# Sheet1.net
KiCad netlist of a schematic drawn in Altium Designer
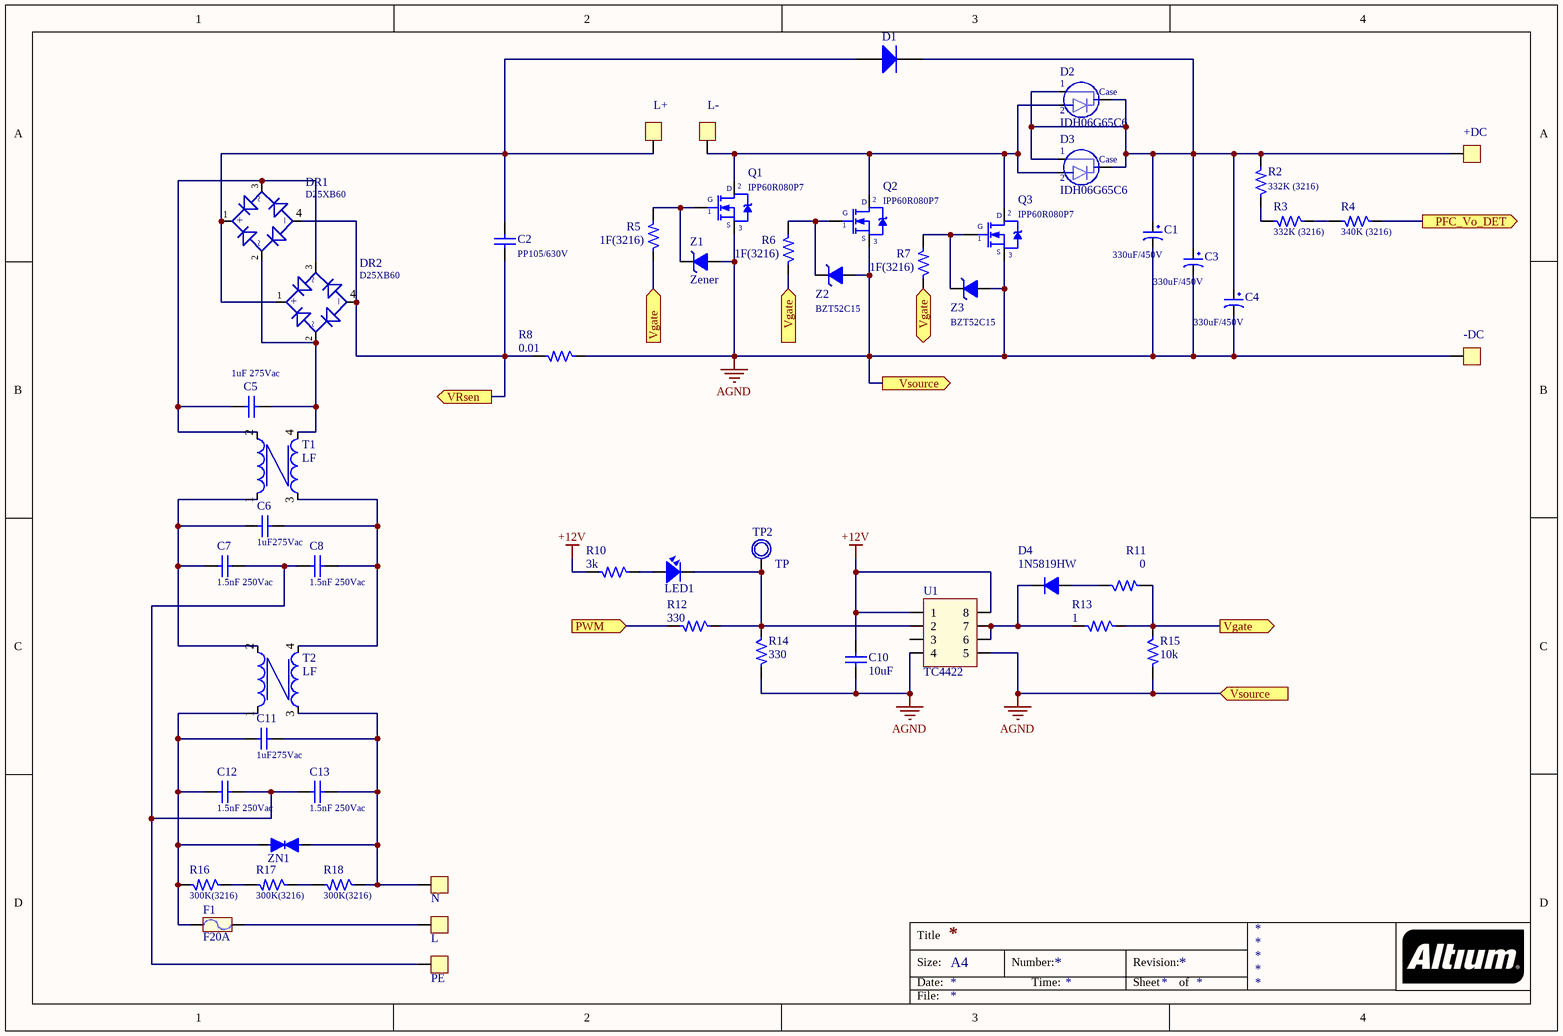
[diagram p0: Sheet1.SchDoc]

(export (version "E")
  (design (tool "Eeschema 10.0.6"))
  (components
    (comp (ref "+DC") (value "ERNI") (footprint "Connector") (libsource (lib "Tien_Lib") (part "Connector")))
    (comp (ref "-DC") (value "ERNI") (footprint "Connector") (libsource (lib "Tien_Lib") (part "Connector")))
    (comp (ref "C1")
      (value "330uF/450V")
      (footprint "Capacitor")
      (description "Cap 10000uF/63V")
      (libsource (lib "syhaunguyen") (part "CP9"))
    )
    (comp (ref "C2")
      (value "PP105/630V")
      (footprint "C1uF 28mm")
      (description "Capacitor (Semiconductor SIM Model)")
      (fields (field (name "PUBLISHER") "Altium Limited"))
      (libsource (lib "syhaunguyen") (part "Cap Semi_3"))
    )
    (comp (ref "C3")
      (value "330uF/450V")
      (footprint "Capacitor")
      (description "Cap 10000uF/63V")
      (libsource (lib "syhaunguyen") (part "CP9"))
    )
    (comp (ref "C4")
      (value "330uF/450V")
      (footprint "Capacitor")
      (description "Cap 10000uF/63V")
      (libsource (lib "syhaunguyen") (part "CP9"))
    )
    (comp (ref "C5")
      (value "1uF 275Vac")
      (footprint "CAP 11x22")
      (description "Capacitor (Semiconductor SIM Model)")
      (fields (field (name "PUBLISHER") "Altium Limited"))
      (libsource (lib "syhaunguyen") (part "Cap Semi_3"))
    )
    (comp (ref "C6")
      (value "1uF275Vac")
      (footprint "CAP 11x22")
      (description "Capacitor (Semiconductor SIM Model)")
      (fields (field (name "PUBLISHER") "Altium Limited"))
      (libsource (lib "syhaunguyen") (part "Cap Semi_3"))
    )
    (comp (ref "C7")
      (value "1.5nF 250Vac")
      (footprint "CN4")
      (description "Capacitor (Semiconductor SIM Model)")
      (fields (field (name "PUBLISHER") "Altium Limited"))
      (libsource (lib "syhaunguyen") (part "Cap Semi_3"))
    )
    (comp (ref "C8")
      (value "1.5nF 250Vac")
      (footprint "CN4")
      (description "Capacitor (Semiconductor SIM Model)")
      (fields (field (name "PUBLISHER") "Altium Limited"))
      (libsource (lib "syhaunguyen") (part "Cap Semi_3"))
    )
    (comp (ref "C10")
      (value "10uF")
      (footprint "SM-CAP-0805")
      (description "Capacitor (Semiconductor SIM Model)")
      (fields (field (name "PUBLISHER") "Altium Limited"))
      (libsource (lib "syhaunguyen") (part "Cap Semi_3"))
    )
    (comp (ref "C11")
      (value "1uF275Vac")
      (footprint "CAP 11x22")
      (description "Capacitor (Semiconductor SIM Model)")
      (fields (field (name "PUBLISHER") "Altium Limited"))
      (libsource (lib "syhaunguyen") (part "Cap Semi_3"))
    )
    (comp (ref "C12")
      (value "1.5nF 250Vac")
      (footprint "CN4")
      (description "Capacitor (Semiconductor SIM Model)")
      (fields (field (name "PUBLISHER") "Altium Limited"))
      (libsource (lib "syhaunguyen") (part "Cap Semi_3"))
    )
    (comp (ref "C13")
      (value "1.5nF 250Vac")
      (footprint "CN4")
      (description "Capacitor (Semiconductor SIM Model)")
      (fields (field (name "PUBLISHER") "Altium Limited"))
      (libsource (lib "syhaunguyen") (part "Cap Semi_3"))
    )
    (comp (ref "D1")
      (value "Diode")
      (footprint "D5AN")
      (description "Default Diode")
      (fields (field (name "PUBLISHER") "Altium Limited"))
      (libsource (lib "syhaunguyen") (part "Diode"))
    )
    (comp (ref "D2")
      (value "IDH06G65C6")
      (footprint "TO-263 Diode")
      (libsource (lib "UC3854") (part "CSD06060"))
    )
    (comp (ref "D3")
      (value "IDH06G65C6")
      (footprint "TO-263 Diode")
      (libsource (lib "UC3854") (part "CSD06060"))
    )
    (comp (ref "D4")
      (value "1N5819HW")
      (footprint "BZT52C15")
      (description "D0.5A")
      (libsource (lib "syhaunguyen") (part "D0.5A"))
    )
    (comp (ref "DR1")
      (value "D25XB60")
      (footprint "D25XB60")
      (libsource (lib "UC3854") (part "Bridge Rectifier"))
    )
    (comp (ref "DR2")
      (value "D25XB60")
      (footprint "D25XB60")
      (libsource (lib "UC3854") (part "Bridge Rectifier"))
    )
    (comp (ref "F1")
      (value "F20A")
      (footprint "Fuse")
      (description "Fuse")
      (fields (field (name "DESIGNED BY") "VanDungEvn"))
      (libsource (lib "syhaunguyen") (part "Fuse"))
    )
    (comp (ref "L") (value "ERNI") (footprint "Connector") (libsource (lib "Tien_Lib") (part "Connector")))
    (comp (ref "L+") (value "ERNI") (footprint "Connector") (libsource (lib "") (part "Connector_1")))
    (comp (ref "L-") (value "ERNI") (footprint "Connector") (libsource (lib "") (part "Connector_1")))
    (comp (ref "LED1")
      (value "LED")
      (footprint "SM-LED-0805-Blue")
      (description "LED Single colour Green and Red")
      (libsource (lib "syhaunguyen") (part "LED"))
    )
    (comp (ref "N") (value "ERNI") (footprint "Connector") (libsource (lib "Tien_Lib") (part "Connector")))
    (comp (ref "PE") (value "ERNI") (footprint "Connector") (libsource (lib "Tien_Lib") (part "Connector")))
    (comp (ref "Q1")
      (value "IPP60R080P7")
      (footprint "TO-263 MOSFET")
      (description "MOSFET N - CHANNEL 500V - 0.75 - 8A - TO-220")
      (libsource (lib "syhaunguyen") (part "IRF840"))
    )
    (comp (ref "Q2")
      (value "IPP60R080P7")
      (footprint "TO-263 MOSFET")
      (description "MOSFET N - CHANNEL 500V - 0.75 - 8A - TO-220")
      (libsource (lib "syhaunguyen") (part "IRF840"))
    )
    (comp (ref "Q3")
      (value "IPP60R080P7")
      (footprint "TO-263 MOSFET")
      (description "MOSFET N - CHANNEL 500V - 0.75 - 8A - TO-220")
      (libsource (lib "syhaunguyen") (part "IRF840"))
    )
    (comp (ref "R2")
      (value "332K (3216)")
      (footprint "SM-RES-1206")
      (description "Resistor 1/4W")
      (libsource (lib "syhaunguyen") (part "R"))
    )
    (comp (ref "R3")
      (value "332K (3216)")
      (footprint "SM-RES-1206")
      (description "Resistor 1/4W")
      (libsource (lib "syhaunguyen") (part "R"))
    )
    (comp (ref "R4")
      (value "340K (3216)")
      (footprint "SM-RES-1206")
      (description "Resistor 1/4W")
      (libsource (lib "syhaunguyen") (part "R"))
    )
    (comp (ref "R5")
      (value "1F(3216)")
      (footprint "SM-RES-1206")
      (description "Resistor 1/4W")
      (libsource (lib "syhaunguyen") (part "R"))
    )
    (comp (ref "R6")
      (value "1F(3216)")
      (footprint "SM-RES-1206")
      (description "Resistor 1/4W")
      (libsource (lib "syhaunguyen") (part "R"))
    )
    (comp (ref "R7")
      (value "1F(3216)")
      (footprint "SM-RES-1206")
      (description "Resistor 1/4W")
      (libsource (lib "syhaunguyen") (part "R"))
    )
    (comp (ref "R8")
      (value "0.01")
      (footprint "WSHM2818")
      (description "Resistor 1/4W")
      (libsource (lib "syhaunguyen") (part "R"))
    )
    (comp (ref "R10")
      (value "3k")
      (footprint "SM-RES-0805")
      (description "Resistor 1/4W")
      (libsource (lib "syhaunguyen") (part "R"))
    )
    (comp (ref "R11")
      (value "0")
      (footprint "SM-RES-1206")
      (description "Resistor 1/4W")
      (libsource (lib "syhaunguyen") (part "R"))
    )
    (comp (ref "R12")
      (value "330")
      (footprint "SM-RES-0805")
      (description "Resistor 1/4W")
      (libsource (lib "syhaunguyen") (part "R"))
    )
    (comp (ref "R13")
      (value "1")
      (footprint "SM-RES-1206")
      (description "Resistor 1/4W")
      (libsource (lib "syhaunguyen") (part "R"))
    )
    (comp (ref "R14")
      (value "330")
      (footprint "SM-RES-0805")
      (description "Resistor 1/4W")
      (libsource (lib "syhaunguyen") (part "R"))
    )
    (comp (ref "R15")
      (value "10k")
      (footprint "SM-RES-0805")
      (description "Resistor 1/4W")
      (libsource (lib "syhaunguyen") (part "R"))
    )
    (comp (ref "R16")
      (value "300K(3216)")
      (footprint "SM-RES-1206")
      (description "Resistor 1/4W")
      (libsource (lib "syhaunguyen") (part "R"))
    )
    (comp (ref "R17")
      (value "300K(3216)")
      (footprint "SM-RES-1206")
      (description "Resistor 1/4W")
      (libsource (lib "syhaunguyen") (part "R"))
    )
    (comp (ref "R18")
      (value "300K(3216)")
      (footprint "SM-RES-1206")
      (description "Resistor 1/4W")
      (libsource (lib "syhaunguyen") (part "R"))
    )
    (comp (ref "T1")
      (value "LF")
      (footprint "EMI tranformer")
      (libsource (lib "UC3854") (part "IEMI filter"))
    )
    (comp (ref "T2")
      (value "LF")
      (footprint "EMI tranformer")
      (libsource (lib "UC3854") (part "IEMI filter"))
    )
    (comp (ref "TP2")
      (value "TP")
      (footprint "TP1")
      (description "Test Point")
      (libsource (lib "syhaunguyen") (part "TP1"))
    )
    (comp (ref "U1")
      (value "TC4422")
      (footprint "TC4422")
      (description "DIP8")
      (libsource (lib "syhaunguyen") (part "DIP8"))
    )
    (comp (ref "Z1") (value "Zener") (footprint "BZT52C15") (libsource (lib "syhaunguyen") (part "Zener")))
    (comp (ref "Z2") (value "BZT52C15") (footprint "BZT52C15") (libsource (lib "syhaunguyen") (part "Zener")))
    (comp (ref "Z3") (value "BZT52C15") (footprint "BZT52C15") (libsource (lib "syhaunguyen") (part "Zener")))
    (comp (ref "ZN1")
      (value "Z")
      (footprint "RT 7mm")
      (description "Zenner Protect AC in")
      (libsource (lib "syhaunguyen") (part "ZN"))
    )
  )
  (nets
    (net (code "1") (name "+12V") (class "Default")
      (node (ref "C10") (pin "1") (pinfunction "1_1") (pintype "passive"))
      (node (ref "R10") (pin "2") (pinfunction "2_2") (pintype "passive"))
      (node (ref "U1") (pin "1") (pinfunction "1_1") (pintype "passive"))
      (node (ref "U1") (pin "8") (pinfunction "8_8") (pintype "passive"))
    )
    (net (code "2") (name "/PFC_Vo_DET") (class "Default")
      (node (ref "R4") (pin "1") (pinfunction "1_1") (pintype "passive"))
    )
    (net (code "3") (name "/PWM") (class "Default")
      (node (ref "R12") (pin "2") (pinfunction "2_2") (pintype "passive"))
    )
    (net (code "4") (name "/VRsen") (class "Default")
      (node (ref "C2") (pin "1") (pinfunction "1_1") (pintype "passive"))
      (node (ref "DR1") (pin "4") (pinfunction "0_4") (pintype "passive"))
      (node (ref "DR2") (pin "4") (pinfunction "0_4") (pintype "passive"))
      (node (ref "R8") (pin "2") (pinfunction "2_2") (pintype "passive"))
    )
    (net (code "5") (name "/Vgate") (class "Default")
      (node (ref "R11") (pin "2") (pinfunction "2_2") (pintype "passive"))
      (node (ref "R13") (pin "1") (pinfunction "1_1") (pintype "passive"))
      (node (ref "R15") (pin "1") (pinfunction "1_1") (pintype "passive"))
      (node (ref "R5") (pin "1") (pinfunction "1_1") (pintype "passive"))
      (node (ref "R6") (pin "1") (pinfunction "1_1") (pintype "passive"))
      (node (ref "R7") (pin "1") (pinfunction "1_1") (pintype "passive"))
    )
    (net (code "6") (name "AGND") (class "Default")
      (node (ref "-DC") (pin "0") (pinfunction "0_0") (pintype "passive"))
      (node (ref "C1") (pin "2") (pinfunction "2_2") (pintype "passive"))
      (node (ref "C10") (pin "2") (pinfunction "2_2") (pintype "passive"))
      (node (ref "C3") (pin "2") (pinfunction "2_2") (pintype "passive"))
      (node (ref "C4") (pin "2") (pinfunction "2_2") (pintype "passive"))
      (node (ref "Q1") (pin "3") (pinfunction "S_3") (pintype "passive"))
      (node (ref "Q2") (pin "3") (pinfunction "S_3") (pintype "passive"))
      (node (ref "Q3") (pin "3") (pinfunction "S_3") (pintype "passive"))
      (node (ref "R14") (pin "2") (pinfunction "2_2") (pintype "passive"))
      (node (ref "R15") (pin "2") (pinfunction "2_2") (pintype "passive"))
      (node (ref "R8") (pin "1") (pinfunction "1_1") (pintype "passive"))
      (node (ref "U1") (pin "4") (pinfunction "4_4") (pintype "passive"))
      (node (ref "U1") (pin "5") (pinfunction "5_5") (pintype "passive"))
      (node (ref "Z1") (pin "1") (pinfunction "A_1") (pintype "passive"))
      (node (ref "Z2") (pin "1") (pinfunction "A_1") (pintype "passive"))
      (node (ref "Z3") (pin "1") (pinfunction "A_1") (pintype "passive"))
    )
    (net (code "7") (name "Net-(C5-Pad1)") (class "Default")
      (node (ref "C5") (pin "1") (pinfunction "1_1") (pintype "passive"))
      (node (ref "DR1") (pin "2") (pinfunction "21_2") (pintype "passive"))
      (node (ref "DR2") (pin "2") (pinfunction "21_2") (pintype "passive"))
      (node (ref "T1") (pin "4") (pinfunction "2_4") (pintype "passive"))
    )
    (net (code "8") (name "Net-(C5-Pad2)") (class "Default")
      (node (ref "C5") (pin "2") (pinfunction "2_2") (pintype "passive"))
      (node (ref "DR1") (pin "3") (pinfunction "21_3") (pintype "passive"))
      (node (ref "DR2") (pin "3") (pinfunction "21_3") (pintype "passive"))
      (node (ref "T1") (pin "2") (pinfunction "2_2") (pintype "passive"))
    )
    (net (code "9") (name "Net-(C6-Pad1)") (class "Default")
      (node (ref "C6") (pin "1") (pinfunction "1_1") (pintype "passive"))
      (node (ref "C7") (pin "2") (pinfunction "2_2") (pintype "passive"))
      (node (ref "T1") (pin "1") (pinfunction "2_1") (pintype "passive"))
      (node (ref "T2") (pin "2") (pinfunction "2_2") (pintype "passive"))
    )
    (net (code "10") (name "Net-(C6-Pad2)") (class "Default")
      (node (ref "C6") (pin "2") (pinfunction "2_2") (pintype "passive"))
      (node (ref "C8") (pin "1") (pinfunction "1_1") (pintype "passive"))
      (node (ref "T1") (pin "3") (pinfunction "2_3") (pintype "passive"))
      (node (ref "T2") (pin "4") (pinfunction "2_4") (pintype "passive"))
    )
    (net (code "11") (name "Net-(C11-Pad1)") (class "Default")
      (node (ref "C11") (pin "1") (pinfunction "1_1") (pintype "passive"))
      (node (ref "C13") (pin "1") (pinfunction "1_1") (pintype "passive"))
      (node (ref "N") (pin "0") (pinfunction "0_0") (pintype "passive"))
      (node (ref "R18") (pin "1") (pinfunction "1_1") (pintype "passive"))
      (node (ref "T2") (pin "3") (pinfunction "2_3") (pintype "passive"))
      (node (ref "ZN1") (pin "2") (pinfunction "2_2") (pintype "passive"))
    )
    (net (code "12") (name "Net-(C11-Pad2)") (class "Default")
      (node (ref "C11") (pin "2") (pinfunction "2_2") (pintype "passive"))
      (node (ref "C12") (pin "2") (pinfunction "2_2") (pintype "passive"))
      (node (ref "F1") (pin "2") (pinfunction "2_2") (pintype "passive"))
      (node (ref "R16") (pin "2") (pinfunction "2_2") (pintype "passive"))
      (node (ref "T2") (pin "1") (pinfunction "2_1") (pintype "passive"))
      (node (ref "ZN1") (pin "1") (pinfunction "1_1") (pintype "passive"))
    )
    (net (code "13") (name "Net-(C12-Pad1)") (class "Default")
      (node (ref "C12") (pin "1") (pinfunction "1_1") (pintype "passive"))
      (node (ref "C13") (pin "2") (pinfunction "2_2") (pintype "passive"))
      (node (ref "C7") (pin "1") (pinfunction "1_1") (pintype "passive"))
      (node (ref "C8") (pin "2") (pinfunction "2_2") (pintype "passive"))
      (node (ref "PE") (pin "0") (pinfunction "0_0") (pintype "passive"))
    )
    (net (code "14") (name "Net-(D1-A)") (class "Default")
      (node (ref "C2") (pin "2") (pinfunction "2_2") (pintype "passive"))
      (node (ref "D1") (pin "1") (pinfunction "A_1") (pintype "passive"))
      (node (ref "DR1") (pin "1") (pinfunction "21_1") (pintype "passive"))
      (node (ref "DR2") (pin "1") (pinfunction "21_1") (pintype "passive"))
      (node (ref "L+") (pin "0") (pinfunction "0_0") (pintype "passive"))
    )
    (net (code "15") (name "Net-(D1-K)") (class "Default")
      (node (ref "+DC") (pin "0") (pinfunction "0_0") (pintype "passive"))
      (node (ref "C1") (pin "1") (pinfunction "1_1") (pintype "passive"))
      (node (ref "C3") (pin "1") (pinfunction "1_1") (pintype "passive"))
      (node (ref "C4") (pin "1") (pinfunction "1_1") (pintype "passive"))
      (node (ref "D1") (pin "2") (pinfunction "K_2") (pintype "passive"))
      (node (ref "D2") (pin "1") (pinfunction "Kathod_1") (pintype "passive"))
      (node (ref "D3") (pin "1") (pinfunction "Kathod_1") (pintype "passive"))
      (node (ref "R2") (pin "2") (pinfunction "2_2") (pintype "passive"))
    )
    (net (code "16") (name "Net-(D2-Anode)") (class "Default")
      (node (ref "D2") (pin "2") (pinfunction "Anode_2") (pintype "passive"))
      (node (ref "D3") (pin "2") (pinfunction "Anode_2") (pintype "passive"))
      (node (ref "L-") (pin "0") (pinfunction "0_0") (pintype "passive"))
      (node (ref "Q1") (pin "2") (pinfunction "D_2") (pintype "passive"))
      (node (ref "Q2") (pin "2") (pinfunction "D_2") (pintype "passive"))
      (node (ref "Q3") (pin "2") (pinfunction "D_2") (pintype "passive"))
    )
    (net (code "17") (name "Net-(D4-A)") (class "Default")
      (node (ref "D4") (pin "1") (pinfunction "A_1") (pintype "passive"))
      (node (ref "R11") (pin "1") (pinfunction "1_1") (pintype "passive"))
    )
    (net (code "18") (name "Net-(D4-K)") (class "Default")
      (node (ref "D4") (pin "2") (pinfunction "K_2") (pintype "passive"))
      (node (ref "R13") (pin "2") (pinfunction "2_2") (pintype "passive"))
      (node (ref "U1") (pin "6") (pinfunction "6_6") (pintype "passive"))
      (node (ref "U1") (pin "7") (pinfunction "7_7") (pintype "passive"))
    )
    (net (code "19") (name "Net-(F1-Pad1)") (class "Default")
      (node (ref "F1") (pin "1") (pinfunction "1_1") (pintype "passive"))
      (node (ref "L") (pin "0") (pinfunction "0_0") (pintype "passive"))
    )
    (net (code "20") (name "Net-(LED1-Pad1)") (class "Default")
      (node (ref "LED1") (pin "1") (pinfunction "1_1") (pintype "passive"))
      (node (ref "R10") (pin "1") (pinfunction "1_1") (pintype "passive"))
    )
    (net (code "21") (name "Net-(LED1-Pad2)") (class "Default")
      (node (ref "LED1") (pin "2") (pinfunction "2_2") (pintype "passive"))
      (node (ref "R12") (pin "1") (pinfunction "1_1") (pintype "passive"))
      (node (ref "R14") (pin "1") (pinfunction "1_1") (pintype "passive"))
      (node (ref "TP2") (pin "1") (pinfunction "1_1") (pintype "passive"))
      (node (ref "U1") (pin "2") (pinfunction "2_2") (pintype "passive"))
    )
    (net (code "22") (name "Net-(Q1-G)") (class "Default")
      (node (ref "Q1") (pin "1") (pinfunction "G_1") (pintype "passive"))
      (node (ref "R5") (pin "2") (pinfunction "2_2") (pintype "passive"))
      (node (ref "Z1") (pin "2") (pinfunction "K_2") (pintype "passive"))
    )
    (net (code "23") (name "Net-(Q2-G)") (class "Default")
      (node (ref "Q2") (pin "1") (pinfunction "G_1") (pintype "passive"))
      (node (ref "R6") (pin "2") (pinfunction "2_2") (pintype "passive"))
      (node (ref "Z2") (pin "2") (pinfunction "K_2") (pintype "passive"))
    )
    (net (code "24") (name "Net-(Q3-G)") (class "Default")
      (node (ref "Q3") (pin "1") (pinfunction "G_1") (pintype "passive"))
      (node (ref "R7") (pin "2") (pinfunction "2_2") (pintype "passive"))
      (node (ref "Z3") (pin "2") (pinfunction "K_2") (pintype "passive"))
    )
    (net (code "25") (name "Net-(R2-Pad1)") (class "Default")
      (node (ref "R2") (pin "1") (pinfunction "1_1") (pintype "passive"))
      (node (ref "R3") (pin "2") (pinfunction "2_2") (pintype "passive"))
    )
    (net (code "26") (name "Net-(R3-Pad1)") (class "Default")
      (node (ref "R3") (pin "1") (pinfunction "1_1") (pintype "passive"))
      (node (ref "R4") (pin "2") (pinfunction "2_2") (pintype "passive"))
    )
    (net (code "27") (name "Net-(R16-Pad1)") (class "Default")
      (node (ref "R16") (pin "1") (pinfunction "1_1") (pintype "passive"))
      (node (ref "R17") (pin "2") (pinfunction "2_2") (pintype "passive"))
    )
    (net (code "28") (name "Net-(R17-Pad1)") (class "Default")
      (node (ref "R17") (pin "1") (pinfunction "1_1") (pintype "passive"))
      (node (ref "R18") (pin "2") (pinfunction "2_2") (pintype "passive"))
    )
    (net (code "29") (name "unconnected-(U1-Pad3)") (class "Default")
      (node (ref "U1") (pin "3") (pinfunction "3_3") (pintype "passive"))
    )
  )
)
